# button_led.net
KiCad netlist of a schematic drawn in Altium Designer
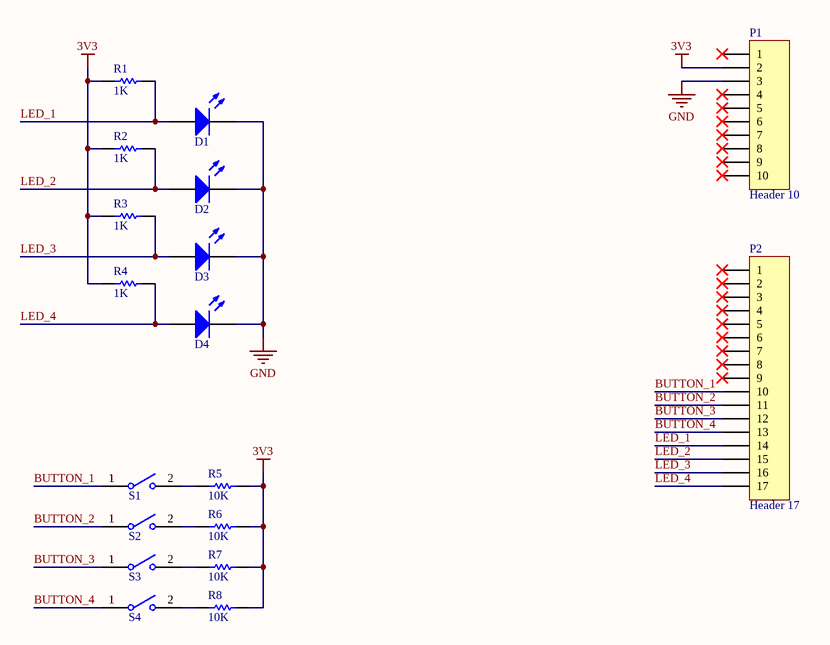
[diagram p0: button_led.SchDoc]

(export (version "E")
  (design (tool "Eeschema 10.0.6"))
  (components
    (comp (ref "D1")
      (value "LED")
      (footprint "0603_YELLOW")
      (description "LED Emitters")
      (libsource (lib "Leds") (part "LED"))
    )
    (comp (ref "D2")
      (value "LED")
      (footprint "0603_YELLOW")
      (description "LED Emitters")
      (libsource (lib "Leds") (part "LED"))
    )
    (comp (ref "D3")
      (value "LED")
      (footprint "0603_YELLOW")
      (description "LED Emitters")
      (libsource (lib "Leds") (part "LED"))
    )
    (comp (ref "D4")
      (value "LED")
      (footprint "0603_YELLOW")
      (description "LED Emitters")
      (libsource (lib "Leds") (part "LED"))
    )
    (comp (ref "P1")
      (value "Header 10")
      (footprint "HDR1X10")
      (description "Header, 10-Pin")
      (fields (field (name "PUBLISHER") "Altium Limited"))
      (libsource (lib "Miscellaneous Connectors") (part "Header 10"))
    )
    (comp (ref "P2")
      (value "Header 17")
      (footprint "HDR1X17")
      (description "Header, 17-Pin")
      (fields (field (name "PUBLISHER") "Altium Limited"))
      (libsource (lib "Miscellaneous Connectors") (part "Header 17"))
    )
    (comp (ref "R1")
      (value "1K")
      (footprint "RC0603N")
      (description "Chip Resistors")
      (fields (field (name "Comment") "RES"))
      (libsource (lib "Resistors") (part "RES"))
    )
    (comp (ref "R2")
      (value "1K")
      (footprint "RC0603N")
      (description "Chip Resistors")
      (fields (field (name "Comment") "RES"))
      (libsource (lib "Resistors") (part "RES"))
    )
    (comp (ref "R3")
      (value "1K")
      (footprint "RC0603N")
      (description "Chip Resistors")
      (fields (field (name "Comment") "RES"))
      (libsource (lib "Resistors") (part "RES"))
    )
    (comp (ref "R4")
      (value "1K")
      (footprint "RC0603N")
      (description "Chip Resistors")
      (fields (field (name "Comment") "RES"))
      (libsource (lib "Resistors") (part "RES"))
    )
    (comp (ref "R5")
      (value "10K")
      (footprint "RC0603N")
      (description "Chip Resistors")
      (fields (field (name "Comment") "RES"))
      (libsource (lib "Resistors") (part "RES"))
    )
    (comp (ref "R6")
      (value "10K")
      (footprint "RC0603N")
      (description "Chip Resistors")
      (fields (field (name "Comment") "RES"))
      (libsource (lib "Resistors") (part "RES"))
    )
    (comp (ref "R7")
      (value "10K")
      (footprint "RC0603N")
      (description "Chip Resistors")
      (fields (field (name "Comment") "RES"))
      (libsource (lib "Resistors") (part "RES"))
    )
    (comp (ref "R8")
      (value "10K")
      (footprint "RC0603N")
      (description "Chip Resistors")
      (fields (field (name "Comment") "RES"))
      (libsource (lib "Resistors") (part "RES"))
    )
    (comp (ref "S1")
      (value "Tact Switch SPST")
      (footprint "TS_SPST_W4.5XD4.5")
      (description "Switch")
      (libsource (lib "Switches") (part "Tact Switch SPST"))
    )
    (comp (ref "S2")
      (value "Tact Switch SPST")
      (footprint "TS_SPST_W4.5XD4.5")
      (description "Switch")
      (libsource (lib "Switches") (part "Tact Switch SPST"))
    )
    (comp (ref "S3")
      (value "Tact Switch SPST")
      (footprint "TS_SPST_W4.5XD4.5")
      (description "Switch")
      (libsource (lib "Switches") (part "Tact Switch SPST"))
    )
    (comp (ref "S4")
      (value "Tact Switch SPST")
      (footprint "TS_SPST_W4.5XD4.5")
      (description "Switch")
      (libsource (lib "Switches") (part "Tact Switch SPST"))
    )
  )
  (nets
    (net (code "1") (name "/BUTTON_1") (class "Default")
      (node (ref "P2") (pin "10") (pinfunction "10_10") (pintype "passive"))
      (node (ref "S1") (pin "1") (pinfunction "1_1") (pintype "passive"))
    )
    (net (code "2") (name "/BUTTON_2") (class "Default")
      (node (ref "P2") (pin "11") (pinfunction "11_11") (pintype "passive"))
      (node (ref "S2") (pin "1") (pinfunction "1_1") (pintype "passive"))
    )
    (net (code "3") (name "/BUTTON_3") (class "Default")
      (node (ref "P2") (pin "12") (pinfunction "12_12") (pintype "passive"))
      (node (ref "S3") (pin "1") (pinfunction "1_1") (pintype "passive"))
    )
    (net (code "4") (name "/BUTTON_4") (class "Default")
      (node (ref "P2") (pin "13") (pinfunction "13_13") (pintype "passive"))
      (node (ref "S4") (pin "1") (pinfunction "1_1") (pintype "passive"))
    )
    (net (code "5") (name "/LED_1") (class "Default")
      (node (ref "D1") (pin "1") (pinfunction "A_1") (pintype "passive"))
      (node (ref "P2") (pin "14") (pinfunction "14_14") (pintype "passive"))
      (node (ref "R1") (pin "1") (pinfunction "1_1") (pintype "passive"))
    )
    (net (code "6") (name "/LED_2") (class "Default")
      (node (ref "D2") (pin "1") (pinfunction "A_1") (pintype "passive"))
      (node (ref "P2") (pin "15") (pinfunction "15_15") (pintype "passive"))
      (node (ref "R2") (pin "1") (pinfunction "1_1") (pintype "passive"))
    )
    (net (code "7") (name "/LED_3") (class "Default")
      (node (ref "D3") (pin "1") (pinfunction "A_1") (pintype "passive"))
      (node (ref "P2") (pin "16") (pinfunction "16_16") (pintype "passive"))
      (node (ref "R3") (pin "1") (pinfunction "1_1") (pintype "passive"))
    )
    (net (code "8") (name "/LED_4") (class "Default")
      (node (ref "D4") (pin "1") (pinfunction "A_1") (pintype "passive"))
      (node (ref "P2") (pin "17") (pinfunction "17_17") (pintype "passive"))
      (node (ref "R4") (pin "1") (pinfunction "1_1") (pintype "passive"))
    )
    (net (code "9") (name "3V3") (class "Default")
      (node (ref "P1") (pin "2") (pinfunction "2_2") (pintype "passive"))
      (node (ref "R1") (pin "2") (pinfunction "2_2") (pintype "passive"))
      (node (ref "R2") (pin "2") (pinfunction "2_2") (pintype "passive"))
      (node (ref "R3") (pin "2") (pinfunction "2_2") (pintype "passive"))
      (node (ref "R4") (pin "2") (pinfunction "2_2") (pintype "passive"))
      (node (ref "R5") (pin "1") (pinfunction "1_1") (pintype "passive"))
      (node (ref "R6") (pin "1") (pinfunction "1_1") (pintype "passive"))
      (node (ref "R7") (pin "1") (pinfunction "1_1") (pintype "passive"))
      (node (ref "R8") (pin "1") (pinfunction "1_1") (pintype "passive"))
    )
    (net (code "10") (name "GND") (class "Default")
      (node (ref "D1") (pin "2") (pinfunction "K_2") (pintype "passive"))
      (node (ref "D2") (pin "2") (pinfunction "K_2") (pintype "passive"))
      (node (ref "D3") (pin "2") (pinfunction "K_2") (pintype "passive"))
      (node (ref "D4") (pin "2") (pinfunction "K_2") (pintype "passive"))
      (node (ref "P1") (pin "3") (pinfunction "3_3") (pintype "passive"))
    )
    (net (code "11") (name "Net-(R5-Pad2)") (class "Default")
      (node (ref "R5") (pin "2") (pinfunction "2_2") (pintype "passive"))
      (node (ref "S1") (pin "2") (pinfunction "2_2") (pintype "passive"))
    )
    (net (code "12") (name "Net-(R6-Pad2)") (class "Default")
      (node (ref "R6") (pin "2") (pinfunction "2_2") (pintype "passive"))
      (node (ref "S2") (pin "2") (pinfunction "2_2") (pintype "passive"))
    )
    (net (code "13") (name "Net-(R7-Pad2)") (class "Default")
      (node (ref "R7") (pin "2") (pinfunction "2_2") (pintype "passive"))
      (node (ref "S3") (pin "2") (pinfunction "2_2") (pintype "passive"))
    )
    (net (code "14") (name "Net-(R8-Pad2)") (class "Default")
      (node (ref "R8") (pin "2") (pinfunction "2_2") (pintype "passive"))
      (node (ref "S4") (pin "2") (pinfunction "2_2") (pintype "passive"))
    )
    (net (code "15") (name "unconnected-(P1-Pad1)") (class "Default")
      (node (ref "P1") (pin "1") (pinfunction "1_1") (pintype "passive+no_connect"))
    )
    (net (code "16") (name "unconnected-(P1-Pad4)") (class "Default")
      (node (ref "P1") (pin "4") (pinfunction "4_4") (pintype "passive+no_connect"))
    )
    (net (code "17") (name "unconnected-(P1-Pad5)") (class "Default")
      (node (ref "P1") (pin "5") (pinfunction "5_5") (pintype "passive+no_connect"))
    )
    (net (code "18") (name "unconnected-(P1-Pad6)") (class "Default")
      (node (ref "P1") (pin "6") (pinfunction "6_6") (pintype "passive+no_connect"))
    )
    (net (code "19") (name "unconnected-(P1-Pad7)") (class "Default")
      (node (ref "P1") (pin "7") (pinfunction "7_7") (pintype "passive+no_connect"))
    )
    (net (code "20") (name "unconnected-(P1-Pad8)") (class "Default")
      (node (ref "P1") (pin "8") (pinfunction "8_8") (pintype "passive+no_connect"))
    )
    (net (code "21") (name "unconnected-(P1-Pad9)") (class "Default")
      (node (ref "P1") (pin "9") (pinfunction "9_9") (pintype "passive+no_connect"))
    )
    (net (code "22") (name "unconnected-(P1-Pad10)") (class "Default")
      (node (ref "P1") (pin "10") (pinfunction "10_10") (pintype "passive+no_connect"))
    )
    (net (code "23") (name "unconnected-(P2-Pad1)") (class "Default")
      (node (ref "P2") (pin "1") (pinfunction "1_1") (pintype "passive+no_connect"))
    )
    (net (code "24") (name "unconnected-(P2-Pad2)") (class "Default")
      (node (ref "P2") (pin "2") (pinfunction "2_2") (pintype "passive+no_connect"))
    )
    (net (code "25") (name "unconnected-(P2-Pad3)") (class "Default")
      (node (ref "P2") (pin "3") (pinfunction "3_3") (pintype "passive+no_connect"))
    )
    (net (code "26") (name "unconnected-(P2-Pad4)") (class "Default")
      (node (ref "P2") (pin "4") (pinfunction "4_4") (pintype "passive+no_connect"))
    )
    (net (code "27") (name "unconnected-(P2-Pad5)") (class "Default")
      (node (ref "P2") (pin "5") (pinfunction "5_5") (pintype "passive+no_connect"))
    )
    (net (code "28") (name "unconnected-(P2-Pad6)") (class "Default")
      (node (ref "P2") (pin "6") (pinfunction "6_6") (pintype "passive+no_connect"))
    )
    (net (code "29") (name "unconnected-(P2-Pad7)") (class "Default")
      (node (ref "P2") (pin "7") (pinfunction "7_7") (pintype "passive+no_connect"))
    )
    (net (code "30") (name "unconnected-(P2-Pad8)") (class "Default")
      (node (ref "P2") (pin "8") (pinfunction "8_8") (pintype "passive+no_connect"))
    )
    (net (code "31") (name "unconnected-(P2-Pad9)") (class "Default")
      (node (ref "P2") (pin "9") (pinfunction "9_9") (pintype "passive+no_connect"))
    )
  )
)
